# S100_Memory_Dumper.net
KiCad netlist of a schematic drawn in Altium Designer
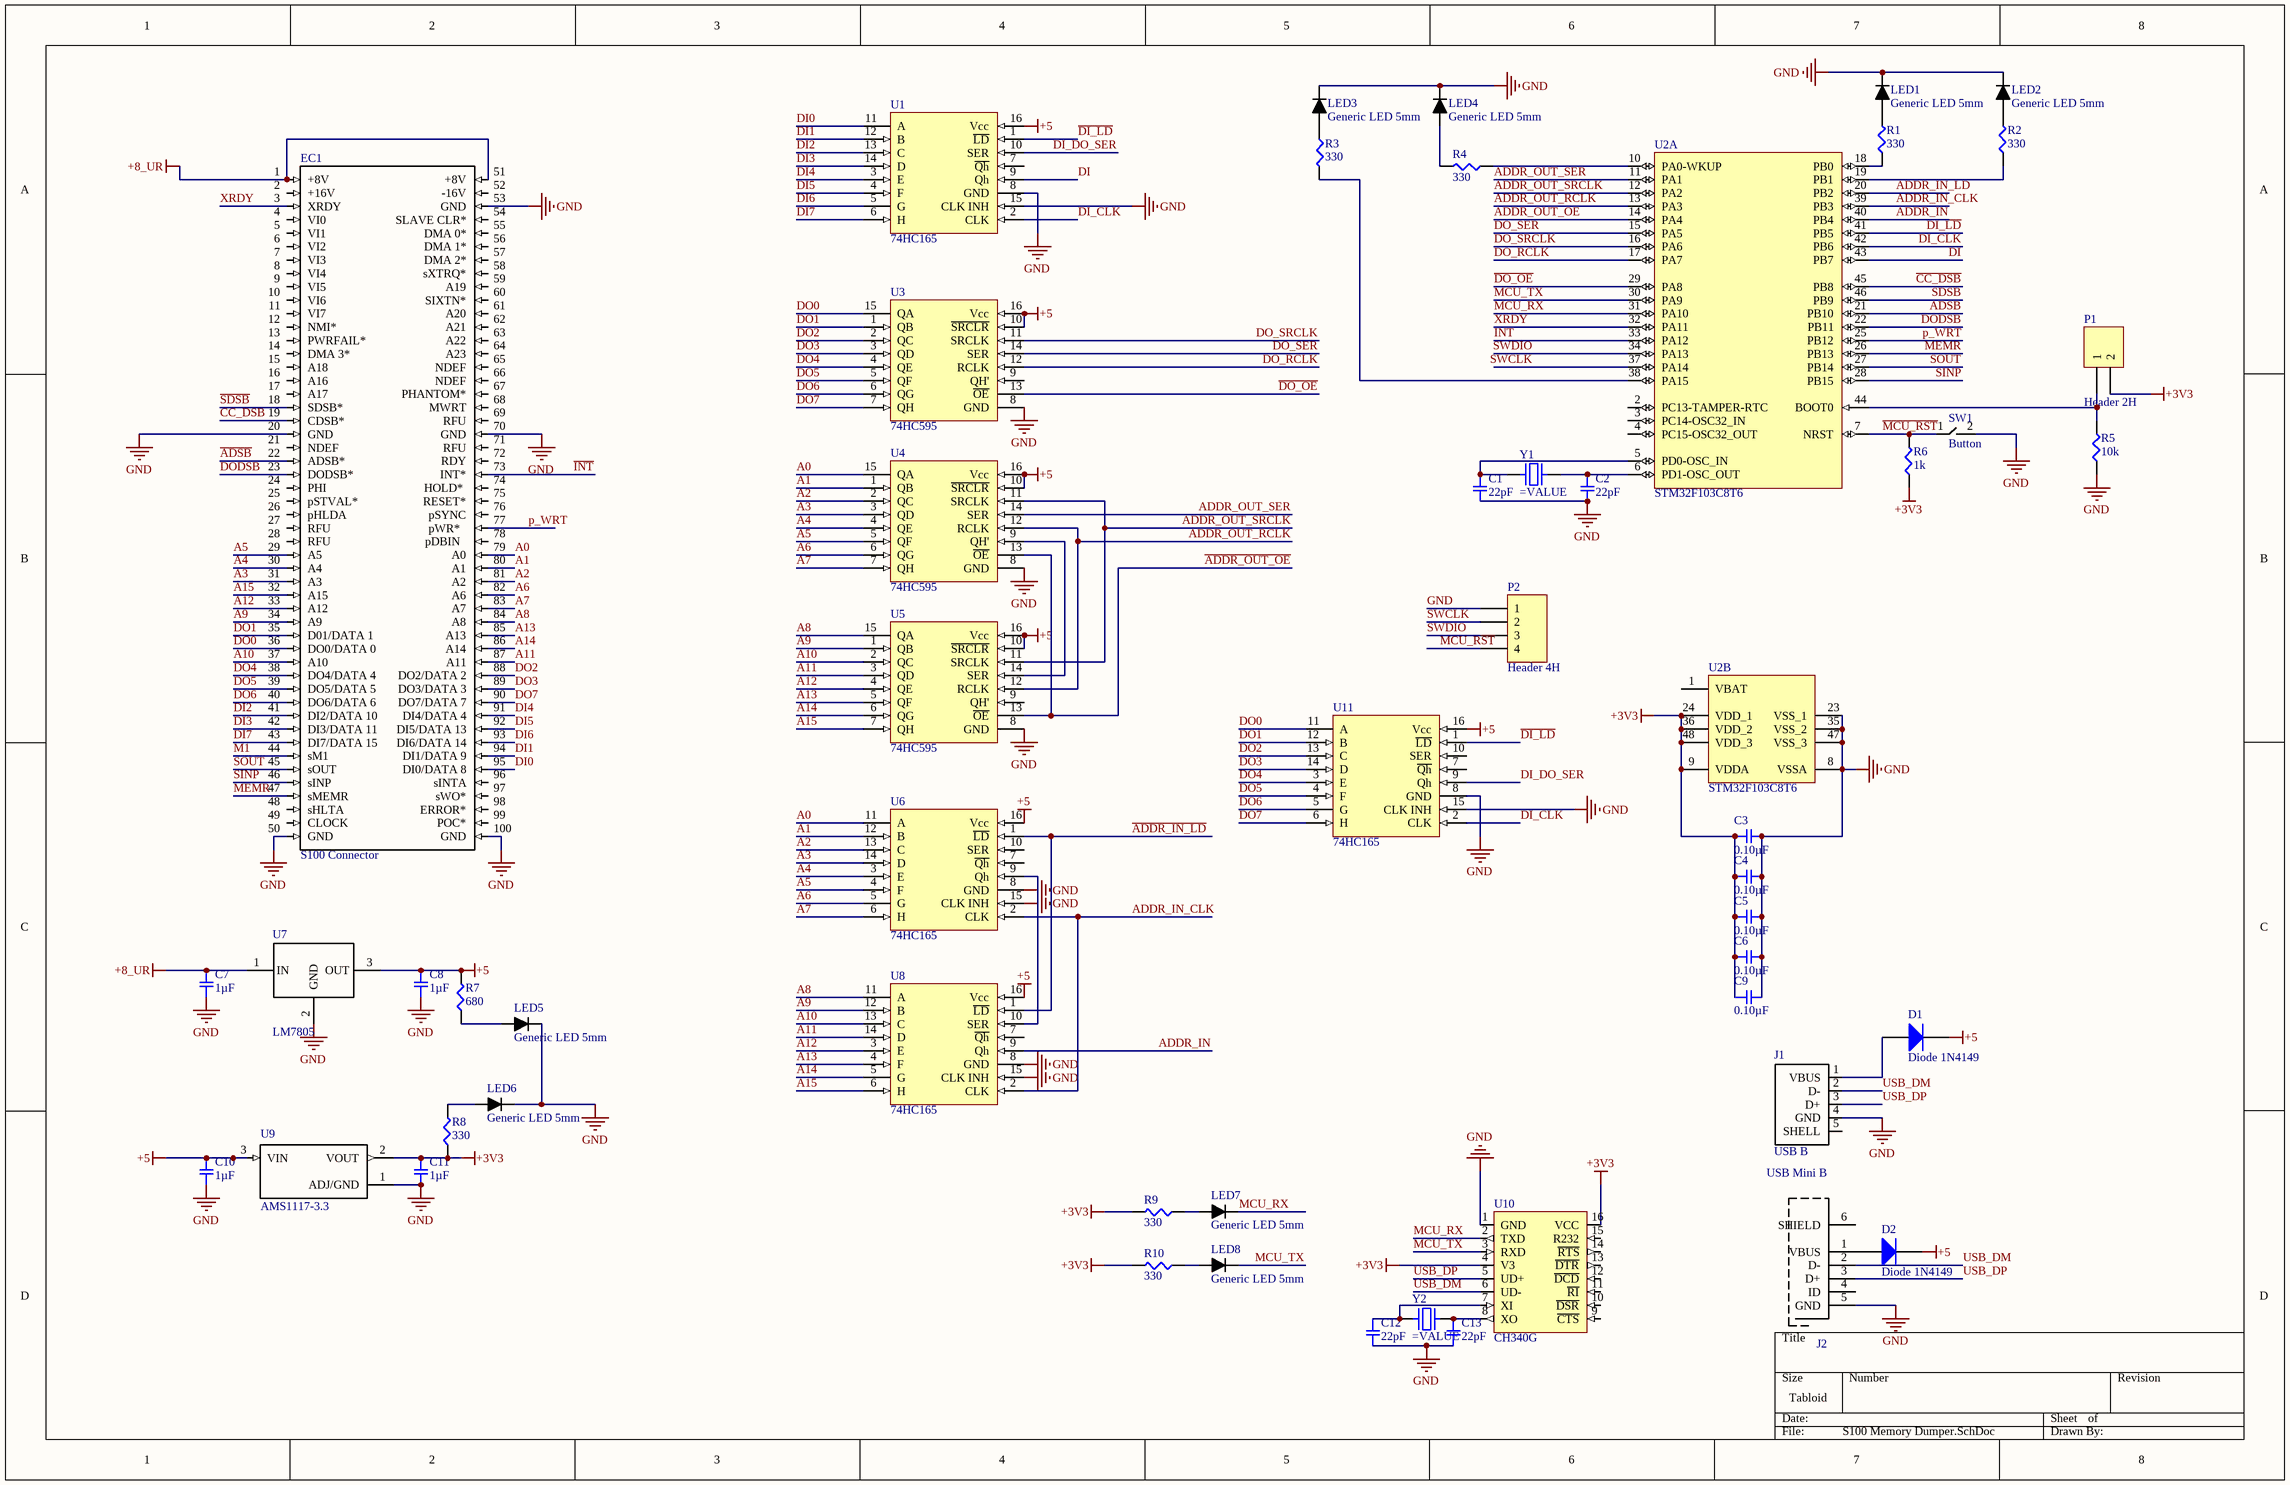
[diagram p0: S100 Memory Dumper.SchDoc]

(export (version "E")
  (design (tool "Eeschema 10.0.6"))
  (components
    (comp (ref "C1")
      (value "22pF")
      (footprint "SMD-0805C")
      (description "CAP CER 22PF 50V NP0 0805")
      (fields
        (field (name "DIGI-KEY PART NUMBER") "490-6097-1-ND")
        (field (name "PART NUMBER") "GQM2195C1H220GB01D")
      )
      (libsource (lib "capacitor_murata_0805") (part "GQM2195C1H220GB01D"))
    )
    (comp (ref "C2")
      (value "22pF")
      (footprint "SMD-0805C")
      (description "CAP CER 22PF 50V NP0 0805")
      (fields
        (field (name "DIGI-KEY PART NUMBER") "490-6097-1-ND")
        (field (name "PART NUMBER") "GQM2195C1H220GB01D")
      )
      (libsource (lib "capacitor_murata_0805") (part "GQM2195C1H220GB01D"))
    )
    (comp (ref "C3")
      (value "0.10µF")
      (footprint "SMD-0805C")
      (description "CAP CER 0.1UF 50V X7R 0805")
      (fields
        (field (name "DIGI-KEY PART NUMBER") "490-11955-1-ND")
        (field (name "PART NUMBER") "GCD21BR71H104KA01L")
      )
      (libsource (lib "capacitor_murata_0805") (part "GCD21BR71H104KA01L"))
    )
    (comp (ref "C4")
      (value "0.10µF")
      (footprint "SMD-0805C")
      (description "CAP CER 0.1UF 50V X7R 0805")
      (fields
        (field (name "DIGI-KEY PART NUMBER") "490-11955-1-ND")
        (field (name "PART NUMBER") "GCD21BR71H104KA01L")
      )
      (libsource (lib "capacitor_murata_0805") (part "GCD21BR71H104KA01L"))
    )
    (comp (ref "C5")
      (value "0.10µF")
      (footprint "SMD-0805C")
      (description "CAP CER 0.1UF 50V X7R 0805")
      (fields
        (field (name "DIGI-KEY PART NUMBER") "490-11955-1-ND")
        (field (name "PART NUMBER") "GCD21BR71H104KA01L")
      )
      (libsource (lib "capacitor_murata_0805") (part "GCD21BR71H104KA01L"))
    )
    (comp (ref "C6")
      (value "0.10µF")
      (footprint "SMD-0805C")
      (description "CAP CER 0.1UF 50V X7R 0805")
      (fields
        (field (name "DIGI-KEY PART NUMBER") "490-11955-1-ND")
        (field (name "PART NUMBER") "GCD21BR71H104KA01L")
      )
      (libsource (lib "capacitor_murata_0805") (part "GCD21BR71H104KA01L"))
    )
    (comp (ref "C7")
      (value "1µF")
      (footprint "SMD-0805C")
      (description "CAP CER 1UF 16V X7R 0805")
      (fields
        (field (name "DIGI-KEY PART NUMBER") "490-5800-1-ND")
        (field (name "PART NUMBER") "GCJ219R71C105KA01D")
      )
      (libsource (lib "capacitor_murata_0805") (part "GCJ219R71C105KA01D"))
    )
    (comp (ref "C8")
      (value "1µF")
      (footprint "SMD-0805C")
      (description "CAP CER 1UF 16V X7R 0805")
      (fields
        (field (name "DIGI-KEY PART NUMBER") "490-5800-1-ND")
        (field (name "PART NUMBER") "GCJ219R71C105KA01D")
      )
      (libsource (lib "capacitor_murata_0805") (part "GCJ219R71C105KA01D"))
    )
    (comp (ref "C9")
      (value "0.10µF")
      (footprint "SMD-0805C")
      (description "CAP CER 0.1UF 50V X7R 0805")
      (fields
        (field (name "DIGI-KEY PART NUMBER") "490-11955-1-ND")
        (field (name "PART NUMBER") "GCD21BR71H104KA01L")
      )
      (libsource (lib "capacitor_murata_0805") (part "GCD21BR71H104KA01L"))
    )
    (comp (ref "C10")
      (value "1µF")
      (footprint "SMD-0805C")
      (description "CAP CER 1UF 16V X7R 0805")
      (fields
        (field (name "DIGI-KEY PART NUMBER") "490-5800-1-ND")
        (field (name "PART NUMBER") "GCJ219R71C105KA01D")
      )
      (libsource (lib "capacitor_murata_0805") (part "GCJ219R71C105KA01D"))
    )
    (comp (ref "C11")
      (value "1µF")
      (footprint "SMD-0805C")
      (description "CAP CER 1UF 16V X7R 0805")
      (fields
        (field (name "DIGI-KEY PART NUMBER") "490-5800-1-ND")
        (field (name "PART NUMBER") "GCJ219R71C105KA01D")
      )
      (libsource (lib "capacitor_murata_0805") (part "GCJ219R71C105KA01D"))
    )
    (comp (ref "C12")
      (value "22pF")
      (footprint "SMD-0805C")
      (description "CAP CER 22PF 50V NP0 0805")
      (fields
        (field (name "DIGI-KEY PART NUMBER") "490-6097-1-ND")
        (field (name "PART NUMBER") "GQM2195C1H220GB01D")
      )
      (libsource (lib "capacitor_murata_0805") (part "GQM2195C1H220GB01D"))
    )
    (comp (ref "C13")
      (value "22pF")
      (footprint "SMD-0805C")
      (description "CAP CER 22PF 50V NP0 0805")
      (fields
        (field (name "DIGI-KEY PART NUMBER") "490-6097-1-ND")
        (field (name "PART NUMBER") "GQM2195C1H220GB01D")
      )
      (libsource (lib "capacitor_murata_0805") (part "GQM2195C1H220GB01D"))
    )
    (comp (ref "D1")
      (value "Diode 1N4149")
      (footprint "DO-35A")
      (description "Computer Diode")
      (fields (field (name "PUBLISHER") "Altium Limited"))
      (libsource (lib "Miscellaneous Devices") (part "Diode 1N4149"))
    )
    (comp (ref "D2")
      (value "Diode 1N4149")
      (footprint "DO-35A")
      (description "Computer Diode")
      (fields (field (name "PUBLISHER") "Altium Limited"))
      (libsource (lib "Miscellaneous Devices") (part "Diode 1N4149"))
    )
    (comp (ref "EC1")
      (value "S100 Connector")
      (footprint "S100")
      (libsource (lib "S100 Breakout SCHLIB") (part "S100 Connector"))
    )
    (comp (ref "J1")
      (value "USB B")
      (footprint "USB B V")
      (libsource (lib "S100 Memory Dumper SCHLIB") (part "USB B"))
    )
    (comp (ref "J2")
      (value "USB Mini B")
      (footprint "USB Mini B")
      (description "MINI USB A - 5POS Horizontal through hole")
      (fields (field (name "MF") "Wurth Electronics") (field (name "MP") "651005136521"))
      (libsource (lib "S100 Memory Dumper SCHLIB") (part "USB Mini B"))
    )
    (comp (ref "LED1")
      (value "Generic LED 5mm")
      (footprint "LED 5mm THT")
      (libsource (lib "Linear Regulators") (part "Generic LED 5mm"))
    )
    (comp (ref "LED2")
      (value "Generic LED 5mm")
      (footprint "LED 5mm THT")
      (libsource (lib "Linear Regulators") (part "Generic LED 5mm"))
    )
    (comp (ref "LED3")
      (value "Generic LED 5mm")
      (footprint "LED 5mm THT")
      (libsource (lib "Linear Regulators") (part "Generic LED 5mm"))
    )
    (comp (ref "LED4")
      (value "Generic LED 5mm")
      (footprint "LED 5mm THT")
      (libsource (lib "Linear Regulators") (part "Generic LED 5mm"))
    )
    (comp (ref "LED5")
      (value "Generic LED 5mm")
      (footprint "LED 5mm THT")
      (libsource (lib "Linear Regulators") (part "Generic LED 5mm"))
    )
    (comp (ref "LED6")
      (value "Generic LED 5mm")
      (footprint "LED 5mm THT")
      (libsource (lib "Linear Regulators") (part "Generic LED 5mm"))
    )
    (comp (ref "LED7")
      (value "Generic LED 5mm")
      (footprint "LED 5mm THT")
      (libsource (lib "Linear Regulators") (part "Generic LED 5mm"))
    )
    (comp (ref "LED8")
      (value "Generic LED 5mm")
      (footprint "LED 5mm THT")
      (libsource (lib "Linear Regulators") (part "Generic LED 5mm"))
    )
    (comp (ref "P1")
      (value "Header 2H")
      (footprint "HDR1X2H")
      (description "Header, 2-Pin, Right Angle")
      (fields (field (name "PUBLISHER") "Altium Limited"))
      (libsource (lib "Miscellaneous Connectors") (part "Header 2H"))
    )
    (comp (ref "P2")
      (value "Header 4H")
      (footprint "HDR1X4H")
      (description "Header, 4-Pin, Right Angle")
      (fields (field (name "PUBLISHER") "Altium Limited"))
      (libsource (lib "Miscellaneous Connectors") (part "Header 4H"))
    )
    (comp (ref "R1")
      (value "330")
      (footprint "SMD-0805-RES")
      (description "RES SMD 330 OHM 1% 1/8W 0805")
      (fields (field (name "PART NUMBER") "ERJ-6ENF3300V") (field (name "DIGI-KEY PART NUMBER") "P330CCT-ND"))
      (libsource (lib "Panasonic_ERJ_0805") (part "ERJ-6ENF3300V"))
    )
    (comp (ref "R2")
      (value "330")
      (footprint "SMD-0805-RES")
      (description "RES SMD 330 OHM 1% 1/8W 0805")
      (fields (field (name "PART NUMBER") "ERJ-6ENF3300V") (field (name "DIGI-KEY PART NUMBER") "P330CCT-ND"))
      (libsource (lib "Panasonic_ERJ_0805") (part "ERJ-6ENF3300V"))
    )
    (comp (ref "R3")
      (value "330")
      (footprint "SMD-0805-RES")
      (description "RES SMD 330 OHM 1% 1/8W 0805")
      (fields (field (name "PART NUMBER") "ERJ-6ENF3300V") (field (name "DIGI-KEY PART NUMBER") "P330CCT-ND"))
      (libsource (lib "Panasonic_ERJ_0805") (part "ERJ-6ENF3300V"))
    )
    (comp (ref "R4")
      (value "330")
      (footprint "SMD-0805-RES")
      (description "RES SMD 330 OHM 1% 1/8W 0805")
      (fields (field (name "PART NUMBER") "ERJ-6ENF3300V") (field (name "DIGI-KEY PART NUMBER") "P330CCT-ND"))
      (libsource (lib "Panasonic_ERJ_0805") (part "ERJ-6ENF3300V"))
    )
    (comp (ref "R5")
      (value "10k")
      (footprint "SMD-0805-RES")
      (description "RES SMD 10K OHM 1% 1/2W 0805")
      (fields
        (field (name "PART NUMBER") "ERJ-P06F1002V")
        (field (name "DIGI-KEY PART NUMBER") "P16059CT-ND")
      )
      (libsource (lib "Panasonic_ERJ_0805") (part "ERJ-P06F1002V"))
    )
    (comp (ref "R6")
      (value "1k")
      (footprint "SMD-0805-RES")
      (description "RES SMD 1K OHM 1% 1/2W 0805")
      (fields
        (field (name "PART NUMBER") "ERJ-P06F1001V")
        (field (name "DIGI-KEY PART NUMBER") "P16058CT-ND")
      )
      (libsource (lib "Panasonic_ERJ_0805") (part "ERJ-P06F1001V"))
    )
    (comp (ref "R7")
      (value "680")
      (footprint "SMD-0805-RES")
      (description "RES SMD 680 OHM 1% 1/8W 0805")
      (fields (field (name "PART NUMBER") "ERJ-6ENF6800V") (field (name "DIGI-KEY PART NUMBER") "P680CCT-ND"))
      (libsource (lib "Panasonic_ERJ_0805") (part "ERJ-6ENF6800V"))
    )
    (comp (ref "R8")
      (value "330")
      (footprint "SMD-0805-RES")
      (description "RES SMD 330 OHM 1% 1/8W 0805")
      (fields (field (name "PART NUMBER") "ERJ-6ENF3300V") (field (name "DIGI-KEY PART NUMBER") "P330CCT-ND"))
      (libsource (lib "Panasonic_ERJ_0805") (part "ERJ-6ENF3300V"))
    )
    (comp (ref "R9")
      (value "330")
      (footprint "SMD-0805-RES")
      (description "RES SMD 330 OHM 1% 1/8W 0805")
      (fields (field (name "PART NUMBER") "ERJ-6ENF3300V") (field (name "DIGI-KEY PART NUMBER") "P330CCT-ND"))
      (libsource (lib "Panasonic_ERJ_0805") (part "ERJ-6ENF3300V"))
    )
    (comp (ref "R10")
      (value "330")
      (footprint "SMD-0805-RES")
      (description "RES SMD 330 OHM 1% 1/8W 0805")
      (fields (field (name "PART NUMBER") "ERJ-6ENF3300V") (field (name "DIGI-KEY PART NUMBER") "P330CCT-ND"))
      (libsource (lib "Panasonic_ERJ_0805") (part "ERJ-6ENF3300V"))
    )
    (comp (ref "SW1")
      (value "Button")
      (footprint "SMD_PUSHBUTTON_LCSC")
      (description "LCSC Push button SMD")
      (libsource (lib "Linear Regulators") (part "Button"))
    )
    (comp (ref "U1")
      (value "74HC165")
      (footprint "S100 Memory Dumper:SOIC-175-16")
      (libsource (lib "S100 Memory Dumper SCHLIB") (part "74HC165"))
    )
    (comp (ref "U2")
      (value "STM32F103C8T6")
      (footprint "STM-LQFP48_N")
      (libsource (lib "STMicroelectronics STM32 F1") (part "STM32F103C8T6"))
    )
    (comp (ref "U3")
      (value "74HC595")
      (footprint "S100 Memory Dumper:SOIC-175-16")
      (libsource (lib "S100 Memory Dumper SCHLIB") (part "74HC595"))
    )
    (comp (ref "U4")
      (value "74HC595")
      (footprint "S100 Memory Dumper:SOIC-175-16")
      (libsource (lib "S100 Memory Dumper SCHLIB") (part "74HC595"))
    )
    (comp (ref "U5")
      (value "74HC595")
      (footprint "S100 Memory Dumper:SOIC-175-16")
      (libsource (lib "S100 Memory Dumper SCHLIB") (part "74HC595"))
    )
    (comp (ref "U6")
      (value "74HC165")
      (footprint "S100 Memory Dumper:SOIC-175-16")
      (libsource (lib "S100 Memory Dumper SCHLIB") (part "74HC165"))
    )
    (comp (ref "U7")
      (value "LM7805")
      (footprint "LM7805-TO220")
      (description "LM7805 Linear Voltage Regulator")
      (libsource (lib "Linear Regulators") (part "LM7805"))
    )
    (comp (ref "U8")
      (value "74HC165")
      (footprint "S100 Memory Dumper:SOIC-175-16")
      (libsource (lib "S100 Memory Dumper SCHLIB") (part "74HC165"))
    )
    (comp (ref "U9")
      (value "AMS1117-3.3")
      (footprint "AMS1117-3.3-SOT23")
      (description "Sot223/Pkg 1-Amp 3.3-Volt Low Drop Out Voltage Regulatator")
      (fields (field (name "MF") "Advanced Monolithic Systems"))
      (libsource (lib "Linear Regulators") (part "AMS1117-3.3"))
    )
    (comp (ref "U10")
      (value "CH340G")
      (footprint "SOIC-175-16")
      (libsource (lib "S100 Memory Dumper SCHLIB") (part "CH340G"))
    )
    (comp (ref "U11")
      (value "74HC165")
      (footprint "S100 Memory Dumper:SOIC-175-16")
      (libsource (lib "S100 Memory Dumper SCHLIB") (part "74HC165"))
    )
    (comp (ref "Y1")
      (value "~")
      (footprint "ABRACON ABLS")
      (description "SMT Crystal")
      (libsource (lib "Linear Regulators") (part "Abracon Crystal ABLS"))
    )
    (comp (ref "Y2")
      (value "~")
      (footprint "THT_Crystal")
      (description "SMT Crystal")
      (libsource (lib "Linear Regulators") (part "THT Crystal"))
    )
  )
  (nets
    (net (code "1") (name "+3V3") (class "Default")
      (node (ref "C11") (pin "1") (pinfunction "1_1") (pintype "passive"))
      (node (ref "C3") (pin "1") (pinfunction "1_1") (pintype "passive"))
      (node (ref "C4") (pin "1") (pinfunction "1_1") (pintype "passive"))
      (node (ref "C5") (pin "1") (pinfunction "1_1") (pintype "passive"))
      (node (ref "C6") (pin "1") (pinfunction "1_1") (pintype "passive"))
      (node (ref "C9") (pin "1") (pinfunction "1_1") (pintype "passive"))
      (node (ref "P1") (pin "2") (pinfunction "2_2") (pintype "passive"))
      (node (ref "R10") (pin "2") (pinfunction "2_2") (pintype "passive"))
      (node (ref "R6") (pin "1") (pinfunction "1_1") (pintype "passive"))
      (node (ref "R8") (pin "1") (pinfunction "1_1") (pintype "passive"))
      (node (ref "R9") (pin "2") (pinfunction "2_2") (pintype "passive"))
      (node (ref "U10") (pin "16") (pinfunction "VCC_16") (pintype "power_in"))
      (node (ref "U10") (pin "4") (pinfunction "V3_4") (pintype "power_in"))
      (node (ref "U2") (pin "24") (pinfunction "VDD_1_24") (pintype "power_in"))
      (node (ref "U2") (pin "36") (pinfunction "VDD_2_36") (pintype "power_in"))
      (node (ref "U2") (pin "48") (pinfunction "VDD_3_48") (pintype "power_in"))
      (node (ref "U2") (pin "9") (pinfunction "VDDA_9") (pintype "power_in"))
      (node (ref "U9") (pin "2") (pinfunction "VOUT_2") (pintype "output"))
    )
    (net (code "2") (name "+5") (class "Default")
      (node (ref "C10") (pin "1") (pinfunction "1_1") (pintype "passive"))
      (node (ref "C8") (pin "1") (pinfunction "1_1") (pintype "passive"))
      (node (ref "D1") (pin "2") (pinfunction "K_2") (pintype "passive"))
      (node (ref "D2") (pin "2") (pinfunction "K_2") (pintype "passive"))
      (node (ref "R7") (pin "2") (pinfunction "2_2") (pintype "passive"))
      (node (ref "U1") (pin "16") (pinfunction "Vcc_16") (pintype "input"))
      (node (ref "U11") (pin "16") (pinfunction "Vcc_16") (pintype "input"))
      (node (ref "U3") (pin "10") (pinfunction "SRCLR_10") (pintype "input"))
      (node (ref "U3") (pin "16") (pinfunction "Vcc_16") (pintype "input"))
      (node (ref "U4") (pin "10") (pinfunction "SRCLR_10") (pintype "input"))
      (node (ref "U4") (pin "16") (pinfunction "Vcc_16") (pintype "input"))
      (node (ref "U5") (pin "10") (pinfunction "SRCLR_10") (pintype "input"))
      (node (ref "U5") (pin "16") (pinfunction "Vcc_16") (pintype "input"))
      (node (ref "U6") (pin "16") (pinfunction "Vcc_16") (pintype "input"))
      (node (ref "U7") (pin "3") (pinfunction "OUT_3") (pintype "passive"))
      (node (ref "U8") (pin "16") (pinfunction "Vcc_16") (pintype "input"))
      (node (ref "U9") (pin "3") (pinfunction "VIN_3") (pintype "input"))
    )
    (net (code "3") (name "+8_UR") (class "Default")
      (node (ref "C7") (pin "1") (pinfunction "1_1") (pintype "passive"))
      (node (ref "EC1") (pin "1") (pinfunction "+8V_1") (pintype "input"))
      (node (ref "EC1") (pin "51") (pinfunction "+8V_51") (pintype "input"))
      (node (ref "U7") (pin "1") (pinfunction "IN_1") (pintype "passive"))
    )
    (net (code "4") (name "/A0") (class "Default")
      (node (ref "EC1") (pin "79") (pinfunction "A0_79") (pintype "input"))
      (node (ref "U4") (pin "15") (pinfunction "QA_15") (pintype "passive"))
      (node (ref "U6") (pin "11") (pinfunction "A_11") (pintype "passive"))
    )
    (net (code "5") (name "/A1") (class "Default")
      (node (ref "EC1") (pin "80") (pinfunction "A1_80") (pintype "input"))
      (node (ref "U4") (pin "1") (pinfunction "QB_1") (pintype "input"))
      (node (ref "U6") (pin "12") (pinfunction "B_12") (pintype "input"))
    )
    (net (code "6") (name "/A2") (class "Default")
      (node (ref "EC1") (pin "81") (pinfunction "A2_81") (pintype "input"))
      (node (ref "U4") (pin "2") (pinfunction "QC_2") (pintype "input"))
      (node (ref "U6") (pin "13") (pinfunction "C_13") (pintype "input"))
    )
    (net (code "7") (name "/A3") (class "Default")
      (node (ref "EC1") (pin "31") (pinfunction "A3_31") (pintype "input"))
      (node (ref "U4") (pin "3") (pinfunction "QD_3") (pintype "input"))
      (node (ref "U6") (pin "14") (pinfunction "D_14") (pintype "input"))
    )
    (net (code "8") (name "/A4") (class "Default")
      (node (ref "EC1") (pin "30") (pinfunction "A4_30") (pintype "input"))
      (node (ref "U4") (pin "4") (pinfunction "QE_4") (pintype "input"))
      (node (ref "U6") (pin "3") (pinfunction "E_3") (pintype "input"))
    )
    (net (code "9") (name "/A5") (class "Default")
      (node (ref "EC1") (pin "29") (pinfunction "A5_29") (pintype "input"))
      (node (ref "U4") (pin "5") (pinfunction "QF_5") (pintype "input"))
      (node (ref "U6") (pin "4") (pinfunction "F_4") (pintype "input"))
    )
    (net (code "10") (name "/A6") (class "Default")
      (node (ref "EC1") (pin "82") (pinfunction "A6_82") (pintype "input"))
      (node (ref "U4") (pin "6") (pinfunction "QG_6") (pintype "input"))
      (node (ref "U6") (pin "5") (pinfunction "G_5") (pintype "passive"))
    )
    (net (code "11") (name "/A7") (class "Default")
      (node (ref "EC1") (pin "83") (pinfunction "A7_83") (pintype "input"))
      (node (ref "U4") (pin "7") (pinfunction "QH_7") (pintype "input"))
      (node (ref "U6") (pin "6") (pinfunction "H_6") (pintype "input"))
    )
    (net (code "12") (name "/A8") (class "Default")
      (node (ref "EC1") (pin "84") (pinfunction "A8_84") (pintype "input"))
      (node (ref "U5") (pin "15") (pinfunction "QA_15") (pintype "passive"))
      (node (ref "U8") (pin "11") (pinfunction "A_11") (pintype "passive"))
    )
    (net (code "13") (name "/A9") (class "Default")
      (node (ref "EC1") (pin "34") (pinfunction "A9_34") (pintype "input"))
      (node (ref "U5") (pin "1") (pinfunction "QB_1") (pintype "input"))
      (node (ref "U8") (pin "12") (pinfunction "B_12") (pintype "input"))
    )
    (net (code "14") (name "/A10") (class "Default")
      (node (ref "EC1") (pin "37") (pinfunction "A10_37") (pintype "input"))
      (node (ref "U5") (pin "2") (pinfunction "QC_2") (pintype "input"))
      (node (ref "U8") (pin "13") (pinfunction "C_13") (pintype "input"))
    )
    (net (code "15") (name "/A11") (class "Default")
      (node (ref "EC1") (pin "87") (pinfunction "A11_87") (pintype "input"))
      (node (ref "U5") (pin "3") (pinfunction "QD_3") (pintype "input"))
      (node (ref "U8") (pin "14") (pinfunction "D_14") (pintype "input"))
    )
    (net (code "16") (name "/A12") (class "Default")
      (node (ref "EC1") (pin "33") (pinfunction "A12_33") (pintype "input"))
      (node (ref "U5") (pin "4") (pinfunction "QE_4") (pintype "input"))
      (node (ref "U8") (pin "3") (pinfunction "E_3") (pintype "input"))
    )
    (net (code "17") (name "/A13") (class "Default")
      (node (ref "EC1") (pin "85") (pinfunction "A13_85") (pintype "input"))
      (node (ref "U5") (pin "5") (pinfunction "QF_5") (pintype "input"))
      (node (ref "U8") (pin "4") (pinfunction "F_4") (pintype "input"))
    )
    (net (code "18") (name "/A14") (class "Default")
      (node (ref "EC1") (pin "86") (pinfunction "A14_86") (pintype "input"))
      (node (ref "U5") (pin "6") (pinfunction "QG_6") (pintype "input"))
      (node (ref "U8") (pin "5") (pinfunction "G_5") (pintype "passive"))
    )
    (net (code "19") (name "/A15") (class "Default")
      (node (ref "EC1") (pin "32") (pinfunction "A15_32") (pintype "input"))
      (node (ref "U5") (pin "7") (pinfunction "QH_7") (pintype "input"))
      (node (ref "U8") (pin "6") (pinfunction "H_6") (pintype "input"))
    )
    (net (code "20") (name "/ADDR_IN") (class "Default")
      (node (ref "U2") (pin "40") (pinfunction "PB4_40") (pintype "bidirectional"))
      (node (ref "U8") (pin "9") (pinfunction "Qh_9") (pintype "input"))
    )
    (net (code "21") (name "/ADDR_IN_CLK") (class "Default")
      (node (ref "U2") (pin "39") (pinfunction "PB3_39") (pintype "bidirectional"))
      (node (ref "U6") (pin "2") (pinfunction "CLK_2") (pintype "input"))
      (node (ref "U8") (pin "2") (pinfunction "CLK_2") (pintype "input"))
    )
    (net (code "22") (name "/ADDR_IN_LD") (class "Default")
      (node (ref "U2") (pin "20") (pinfunction "PB2_20") (pintype "bidirectional"))
      (node (ref "U6") (pin "1") (pinfunction "LD_1") (pintype "input"))
      (node (ref "U8") (pin "1") (pinfunction "LD_1") (pintype "input"))
    )
    (net (code "23") (name "/ADDR_OUT_OE") (class "Default")
      (node (ref "U2") (pin "14") (pinfunction "PA4_14") (pintype "bidirectional"))
      (node (ref "U4") (pin "13") (pinfunction "OE_13") (pintype "passive"))
      (node (ref "U5") (pin "13") (pinfunction "OE_13") (pintype "passive"))
    )
    (net (code "24") (name "/ADDR_OUT_RCLK") (class "Default")
      (node (ref "U2") (pin "13") (pinfunction "PA3_13") (pintype "bidirectional"))
      (node (ref "U4") (pin "12") (pinfunction "RCLK_12") (pintype "input"))
      (node (ref "U5") (pin "12") (pinfunction "RCLK_12") (pintype "input"))
    )
    (net (code "25") (name "/ADDR_OUT_SER") (class "Default")
      (node (ref "U2") (pin "11") (pinfunction "PA1_11") (pintype "bidirectional"))
      (node (ref "U4") (pin "14") (pinfunction "SER_14") (pintype "input"))
    )
    (net (code "26") (name "/ADDR_OUT_SRCLK") (class "Default")
      (node (ref "U2") (pin "12") (pinfunction "PA2_12") (pintype "bidirectional"))
      (node (ref "U4") (pin "11") (pinfunction "SRCLK_11") (pintype "input"))
      (node (ref "U5") (pin "11") (pinfunction "SRCLK_11") (pintype "input"))
    )
    (net (code "27") (name "/ADSB") (class "Default")
      (node (ref "EC1") (pin "22") (pinfunction "ADSB*_22") (pintype "input"))
      (node (ref "U2") (pin "21") (pinfunction "PB10_21") (pintype "bidirectional"))
    )
    (net (code "28") (name "/CC_DSB") (class "Default")
      (node (ref "EC1") (pin "19") (pinfunction "CDSB*_19") (pintype "input"))
      (node (ref "U2") (pin "45") (pinfunction "PB8_45") (pintype "bidirectional"))
    )
    (net (code "29") (name "/DI") (class "Default")
      (node (ref "U1") (pin "9") (pinfunction "Qh_9") (pintype "input"))
      (node (ref "U2") (pin "43") (pinfunction "PB7_43") (pintype "bidirectional"))
    )
    (net (code "30") (name "/DI0") (class "Default")
      (node (ref "EC1") (pin "95") (pinfunction "DI0/DATA_8_95") (pintype "input"))
      (node (ref "U1") (pin "11") (pinfunction "A_11") (pintype "passive"))
    )
    (net (code "31") (name "/DI1") (class "Default")
      (node (ref "EC1") (pin "94") (pinfunction "DI1/DATA_9_94") (pintype "input"))
      (node (ref "U1") (pin "12") (pinfunction "B_12") (pintype "input"))
    )
    (net (code "32") (name "/DI2") (class "Default")
      (node (ref "EC1") (pin "41") (pinfunction "DI2/DATA_10_41") (pintype "input"))
      (node (ref "U1") (pin "13") (pinfunction "C_13") (pintype "input"))
    )
    (net (code "33") (name "/DI3") (class "Default")
      (node (ref "EC1") (pin "42") (pinfunction "DI3/DATA_11_42") (pintype "input"))
      (node (ref "U1") (pin "14") (pinfunction "D_14") (pintype "input"))
    )
    (net (code "34") (name "/DI4") (class "Default")
      (node (ref "EC1") (pin "91") (pinfunction "DI4/DATA_4_91") (pintype "input"))
      (node (ref "U1") (pin "3") (pinfunction "E_3") (pintype "input"))
    )
    (net (code "35") (name "/DI5") (class "Default")
      (node (ref "EC1") (pin "92") (pinfunction "DI5/DATA_13_92") (pintype "input"))
      (node (ref "U1") (pin "4") (pinfunction "F_4") (pintype "input"))
    )
    (net (code "36") (name "/DI6") (class "Default")
      (node (ref "EC1") (pin "93") (pinfunction "DI6/DATA_14_93") (pintype "input"))
      (node (ref "U1") (pin "5") (pinfunction "G_5") (pintype "passive"))
    )
    (net (code "37") (name "/DI7") (class "Default")
      (node (ref "EC1") (pin "43") (pinfunction "DI7/DATA_15_43") (pintype "input"))
      (node (ref "U1") (pin "6") (pinfunction "H_6") (pintype "input"))
    )
    (net (code "38") (name "/DI_CLK") (class "Default")
      (node (ref "U1") (pin "2") (pinfunction "CLK_2") (pintype "input"))
      (node (ref "U11") (pin "2") (pinfunction "CLK_2") (pintype "input"))
      (node (ref "U2") (pin "42") (pinfunction "PB6_42") (pintype "bidirectional"))
    )
    (net (code "39") (name "/DI_DO_SER") (class "Default")
      (node (ref "U1") (pin "10") (pinfunction "SER_10") (pintype "input"))
      (node (ref "U11") (pin "9") (pinfunction "Qh_9") (pintype "input"))
    )
    (net (code "40") (name "/DI_LD") (class "Default")
      (node (ref "U1") (pin "1") (pinfunction "LD_1") (pintype "input"))
      (node (ref "U11") (pin "1") (pinfunction "LD_1") (pintype "input"))
      (node (ref "U2") (pin "41") (pinfunction "PB5_41") (pintype "bidirectional"))
    )
    (net (code "41") (name "/DO0") (class "Default")
      (node (ref "EC1") (pin "36") (pinfunction "DO0/DATA_0_36") (pintype "input"))
      (node (ref "U11") (pin "11") (pinfunction "A_11") (pintype "passive"))
      (node (ref "U3") (pin "15") (pinfunction "QA_15") (pintype "passive"))
    )
    (net (code "42") (name "/DO1") (class "Default")
      (node (ref "EC1") (pin "35") (pinfunction "D01/DATA_1_35") (pintype "input"))
      (node (ref "U11") (pin "12") (pinfunction "B_12") (pintype "input"))
      (node (ref "U3") (pin "1") (pinfunction "QB_1") (pintype "input"))
    )
    (net (code "43") (name "/DO2") (class "Default")
      (node (ref "EC1") (pin "88") (pinfunction "DO2/DATA_2_88") (pintype "input"))
      (node (ref "U11") (pin "13") (pinfunction "C_13") (pintype "input"))
      (node (ref "U3") (pin "2") (pinfunction "QC_2") (pintype "input"))
    )
    (net (code "44") (name "/DO3") (class "Default")
      (node (ref "EC1") (pin "89") (pinfunction "DO3/DATA_3_89") (pintype "input"))
      (node (ref "U11") (pin "14") (pinfunction "D_14") (pintype "input"))
      (node (ref "U3") (pin "3") (pinfunction "QD_3") (pintype "input"))
    )
    (net (code "45") (name "/DO4") (class "Default")
      (node (ref "EC1") (pin "38") (pinfunction "DO4/DATA_4_38") (pintype "input"))
      (node (ref "U11") (pin "3") (pinfunction "E_3") (pintype "input"))
      (node (ref "U3") (pin "4") (pinfunction "QE_4") (pintype "input"))
    )
    (net (code "46") (name "/DO5") (class "Default")
      (node (ref "EC1") (pin "39") (pinfunction "DO5/DATA_5_39") (pintype "input"))
      (node (ref "U11") (pin "4") (pinfunction "F_4") (pintype "input"))
      (node (ref "U3") (pin "5") (pinfunction "QF_5") (pintype "input"))
    )
    (net (code "47") (name "/DO6") (class "Default")
      (node (ref "EC1") (pin "40") (pinfunction "DO6/DATA_6_40") (pintype "input"))
      (node (ref "U11") (pin "5") (pinfunction "G_5") (pintype "passive"))
      (node (ref "U3") (pin "6") (pinfunction "QG_6") (pintype "input"))
    )
    (net (code "48") (name "/DO7") (class "Default")
      (node (ref "EC1") (pin "90") (pinfunction "DO7/DATA_7_90") (pintype "input"))
      (node (ref "U11") (pin "6") (pinfunction "H_6") (pintype "input"))
      (node (ref "U3") (pin "7") (pinfunction "QH_7") (pintype "input"))
    )
    (net (code "49") (name "/DODSB") (class "Default")
      (node (ref "EC1") (pin "23") (pinfunction "DODSB*_23") (pintype "input"))
      (node (ref "U2") (pin "22") (pinfunction "PB11_22") (pintype "bidirectional"))
    )
    (net (code "50") (name "/DO_OE") (class "Default")
      (node (ref "U2") (pin "29") (pinfunction "PA8_29") (pintype "bidirectional"))
      (node (ref "U3") (pin "13") (pinfunction "OE_13") (pintype "passive"))
    )
    (net (code "51") (name "/DO_RCLK") (class "Default")
      (node (ref "U2") (pin "17") (pinfunction "PA7_17") (pintype "bidirectional"))
      (node (ref "U3") (pin "12") (pinfunction "RCLK_12") (pintype "input"))
    )
    (net (code "52") (name "/DO_SER") (class "Default")
      (node (ref "U2") (pin "15") (pinfunction "PA5_15") (pintype "bidirectional"))
      (node (ref "U3") (pin "14") (pinfunction "SER_14") (pintype "input"))
    )
    (net (code "53") (name "/DO_SRCLK") (class "Default")
      (node (ref "U2") (pin "16") (pinfunction "PA6_16") (pintype "bidirectional"))
      (node (ref "U3") (pin "11") (pinfunction "SRCLK_11") (pintype "input"))
    )
    (net (code "54") (name "/INT") (class "Default")
      (node (ref "EC1") (pin "73") (pinfunction "INT*_73") (pintype "input"))
      (node (ref "U2") (pin "33") (pinfunction "PA12_33") (pintype "bidirectional"))
    )
    (net (code "55") (name "/M1") (class "Default")
      (node (ref "EC1") (pin "44") (pinfunction "sM1_44") (pintype "input"))
    )
    (net (code "56") (name "/MCU_RST") (class "Default")
      (node (ref "P2") (pin "4") (pinfunction "4_4") (pintype "passive"))
      (node (ref "R6") (pin "2") (pinfunction "2_2") (pintype "passive"))
      (node (ref "SW1") (pin "1") (pintype "passive"))
      (node (ref "U2") (pin "7") (pinfunction "NRST_7") (pintype "bidirectional"))
    )
    (net (code "57") (name "/MCU_RX") (class "Default")
      (node (ref "LED7") (pin "2") (pinfunction "K_2") (pintype "passive"))
      (node (ref "U10") (pin "2") (pinfunction "TXD_2") (pintype "output"))
      (node (ref "U2") (pin "31") (pinfunction "PA10_31") (pintype "bidirectional"))
    )
    (net (code "58") (name "/MCU_TX") (class "Default")
      (node (ref "LED8") (pin "2") (pinfunction "K_2") (pintype "passive"))
      (node (ref "U10") (pin "3") (pinfunction "RXD_3") (pintype "input"))
      (node (ref "U2") (pin "30") (pinfunction "PA9_30") (pintype "bidirectional"))
    )
    (net (code "59") (name "/MEMR") (class "Default")
      (node (ref "EC1") (pin "47") (pinfunction "sMEMR_47") (pintype "input"))
      (node (ref "U2") (pin "26") (pinfunction "PB13_26") (pintype "bidirectional"))
    )
    (net (code "60") (name "/SDSB") (class "Default")
      (node (ref "EC1") (pin "18") (pinfunction "SDSB*_18") (pintype "input"))
      (node (ref "U2") (pin "46") (pinfunction "PB9_46") (pintype "bidirectional"))
    )
    (net (code "61") (name "/SINP") (class "Default")
      (node (ref "EC1") (pin "46") (pinfunction "sINP_46") (pintype "input"))
      (node (ref "U2") (pin "28") (pinfunction "PB15_28") (pintype "bidirectional"))
    )
    (net (code "62") (name "/SOUT") (class "Default")
      (node (ref "EC1") (pin "45") (pinfunction "sOUT_45") (pintype "input"))
      (node (ref "U2") (pin "27") (pinfunction "PB14_27") (pintype "bidirectional"))
    )
    (net (code "63") (name "/SWCLK") (class "Default")
      (node (ref "P2") (pin "2") (pinfunction "2_2") (pintype "passive"))
      (node (ref "U2") (pin "37") (pinfunction "PA14_37") (pintype "bidirectional"))
    )
    (net (code "64") (name "/SWDIO") (class "Default")
      (node (ref "P2") (pin "3") (pinfunction "3_3") (pintype "passive"))
      (node (ref "U2") (pin "34") (pinfunction "PA13_34") (pintype "bidirectional"))
    )
    (net (code "65") (name "/USB_DM") (class "Default")
      (node (ref "J1") (pin "2") (pinfunction "D-_2") (pintype "passive"))
      (node (ref "J2") (pin "2") (pinfunction "D-_2") (pintype "passive"))
      (node (ref "U10") (pin "6") (pinfunction "UD-_6") (pintype "bidirectional"))
    )
    (net (code "66") (name "/USB_DP") (class "Default")
      (node (ref "J1") (pin "3") (pinfunction "D+_3") (pintype "passive"))
      (node (ref "J2") (pin "3") (pinfunction "D+_3") (pintype "passive"))
      (node (ref "U10") (pin "5") (pinfunction "UD+_5") (pintype "bidirectional"))
    )
    (net (code "67") (name "/XRDY") (class "Default")
      (node (ref "EC1") (pin "3") (pinfunction "XRDY_3") (pintype "input"))
      (node (ref "U2") (pin "32") (pinfunction "PA11_32") (pintype "bidirectional"))
    )
    (net (code "68") (name "/p_WRT") (class "Default")
      (node (ref "EC1") (pin "77") (pinfunction "pWR*  _77") (pintype "input"))
      (node (ref "U2") (pin "25") (pinfunction "PB12_25") (pintype "bidirectional"))
    )
    (net (code "69") (name "GND") (class "Default")
      (node (ref "C1") (pin "2") (pinfunction "2_2") (pintype "passive"))
      (node (ref "C10") (pin "2") (pinfunction "2_2") (pintype "passive"))
      (node (ref "C11") (pin "2") (pinfunction "2_2") (pintype "passive"))
      (node (ref "C12") (pin "2") (pinfunction "2_2") (pintype "passive"))
      (node (ref "C13") (pin "2") (pinfunction "2_2") (pintype "passive"))
      (node (ref "C2") (pin "2") (pinfunction "2_2") (pintype "passive"))
      (node (ref "C3") (pin "2") (pinfunction "2_2") (pintype "passive"))
      (node (ref "C4") (pin "2") (pinfunction "2_2") (pintype "passive"))
      (node (ref "C5") (pin "2") (pinfunction "2_2") (pintype "passive"))
      (node (ref "C6") (pin "2") (pinfunction "2_2") (pintype "passive"))
      (node (ref "C7") (pin "2") (pinfunction "2_2") (pintype "passive"))
      (node (ref "C8") (pin "2") (pinfunction "2_2") (pintype "passive"))
      (node (ref "C9") (pin "2") (pinfunction "2_2") (pintype "passive"))
      (node (ref "EC1") (pin "100") (pinfunction "GND_100") (pintype "input"))
      (node (ref "EC1") (pin "20") (pinfunction "GND_20") (pintype "input"))
      (node (ref "EC1") (pin "50") (pinfunction "GND_50") (pintype "input"))
      (node (ref "EC1") (pin "53") (pinfunction "GND_53") (pintype "input"))
      (node (ref "EC1") (pin "70") (pinfunction "GND_70") (pintype "input"))
      (node (ref "J1") (pin "4") (pinfunction "GND_4") (pintype "passive"))
      (node (ref "J2") (pin "5") (pinfunction "GND_5") (pintype "passive"))
      (node (ref "LED1") (pin "2") (pinfunction "K_2") (pintype "passive"))
      (node (ref "LED2") (pin "2") (pinfunction "K_2") (pintype "passive"))
      (node (ref "LED3") (pin "2") (pinfunction "K_2") (pintype "passive"))
      (node (ref "LED4") (pin "2") (pinfunction "K_2") (pintype "passive"))
      (node (ref "LED5") (pin "2") (pinfunction "K_2") (pintype "passive"))
      (node (ref "LED6") (pin "2") (pinfunction "K_2") (pintype "passive"))
      (node (ref "P2") (pin "1") (pinfunction "1_1") (pintype "passive"))
      (node (ref "R5") (pin "1") (pinfunction "1_1") (pintype "passive"))
      (node (ref "SW1") (pin "2") (pinfunction "2_2") (pintype "passive"))
      (node (ref "U1") (pin "15") (pinfunction "CLK_INH_15") (pintype "input"))
      (node (ref "U1") (pin "8") (pinfunction "GND_8") (pintype "passive"))
      (node (ref "U10") (pin "1") (pinfunction "GND_1") (pintype "power_in"))
      (node (ref "U11") (pin "15") (pinfunction "CLK_INH_15") (pintype "input"))
      (node (ref "U11") (pin "8") (pinfunction "GND_8") (pintype "passive"))
      (node (ref "U2") (pin "23") (pinfunction "VSS_1_23") (pintype "power_in"))
      (node (ref "U2") (pin "35") (pinfunction "VSS_2_35") (pintype "power_in"))
      (node (ref "U2") (pin "47") (pinfunction "VSS_3_47") (pintype "power_in"))
      (node (ref "U2") (pin "8") (pinfunction "VSSA_8") (pintype "power_in"))
      (node (ref "U3") (pin "8") (pinfunction "GND_8") (pintype "passive"))
      (node (ref "U4") (pin "8") (pinfunction "GND_8") (pintype "passive"))
      (node (ref "U5") (pin "8") (pinfunction "GND_8") (pintype "passive"))
      (node (ref "U6") (pin "15") (pinfunction "CLK_INH_15") (pintype "input"))
      (node (ref "U6") (pin "8") (pinfunction "GND_8") (pintype "passive"))
      (node (ref "U7") (pin "2") (pinfunction "GND_2") (pintype "passive"))
      (node (ref "U8") (pin "15") (pinfunction "CLK_INH_15") (pintype "input"))
      (node (ref "U8") (pin "8") (pinfunction "GND_8") (pintype "passive"))
      (node (ref "U9") (pin "1") (pinfunction "ADJ/GND_1") (pintype "power_in"))
    )
    (net (code "70") (name "Net-(D1-A)") (class "Default")
      (node (ref "D1") (pin "1") (pinfunction "A_1") (pintype "passive"))
      (node (ref "J1") (pin "1") (pinfunction "VBUS_1") (pintype "passive"))
    )
    (net (code "71") (name "Net-(D2-A)") (class "Default")
      (node (ref "D2") (pin "1") (pinfunction "A_1") (pintype "passive"))
      (node (ref "J2") (pin "1") (pinfunction "VBUS_1") (pintype "passive"))
    )
    (net (code "72") (name "Net-(LED1-A)") (class "Default")
      (node (ref "LED1") (pin "1") (pinfunction "A_1") (pintype "passive"))
      (node (ref "R1") (pin "2") (pinfunction "2_2") (pintype "passive"))
    )
    (net (code "73") (name "Net-(LED2-A)") (class "Default")
      (node (ref "LED2") (pin "1") (pinfunction "A_1") (pintype "passive"))
      (node (ref "R2") (pin "2") (pinfunction "2_2") (pintype "passive"))
    )
    (net (code "74") (name "Net-(LED3-A)") (class "Default")
      (node (ref "LED3") (pin "1") (pinfunction "A_1") (pintype "passive"))
      (node (ref "R3") (pin "1") (pinfunction "1_1") (pintype "passive"))
    )
    (net (code "75") (name "Net-(LED4-A)") (class "Default")
      (node (ref "LED4") (pin "1") (pinfunction "A_1") (pintype "passive"))
      (node (ref "R4") (pin "2") (pinfunction "2_2") (pintype "passive"))
    )
    (net (code "76") (name "Net-(LED5-A)") (class "Default")
      (node (ref "LED5") (pin "1") (pinfunction "A_1") (pintype "passive"))
      (node (ref "R7") (pin "1") (pinfunction "1_1") (pintype "passive"))
    )
    (net (code "77") (name "Net-(LED6-A)") (class "Default")
      (node (ref "LED6") (pin "1") (pinfunction "A_1") (pintype "passive"))
      (node (ref "R8") (pin "2") (pinfunction "2_2") (pintype "passive"))
    )
    (net (code "78") (name "Net-(LED7-A)") (class "Default")
      (node (ref "LED7") (pin "1") (pinfunction "A_1") (pintype "passive"))
      (node (ref "R9") (pin "1") (pinfunction "1_1") (pintype "passive"))
    )
    (net (code "79") (name "Net-(LED8-A)") (class "Default")
      (node (ref "LED8") (pin "1") (pinfunction "A_1") (pintype "passive"))
      (node (ref "R10") (pin "1") (pinfunction "1_1") (pintype "passive"))
    )
    (net (code "80") (name "Net-(U2A-BOOT0)") (class "Default")
      (node (ref "P1") (pin "1") (pinfunction "1_1") (pintype "passive"))
      (node (ref "R5") (pin "2") (pinfunction "2_2") (pintype "passive"))
      (node (ref "U2") (pin "44") (pinfunction "BOOT0_44") (pintype "input"))
    )
    (net (code "81") (name "Net-(U2A-PA0-WKUP)") (class "Default")
      (node (ref "R4") (pin "1") (pinfunction "1_1") (pintype "passive"))
      (node (ref "U2") (pin "10") (pinfunction "PA0-WKUP_10") (pintype "bidirectional"))
    )
    (net (code "82") (name "Net-(U2A-PA15)") (class "Default")
      (node (ref "R3") (pin "2") (pinfunction "2_2") (pintype "passive"))
      (node (ref "U2") (pin "38") (pinfunction "PA15_38") (pintype "bidirectional"))
    )
    (net (code "83") (name "Net-(U2A-PB0)") (class "Default")
      (node (ref "R1") (pin "1") (pinfunction "1_1") (pintype "passive"))
      (node (ref "U2") (pin "18") (pinfunction "PB0_18") (pintype "bidirectional"))
    )
    (net (code "84") (name "Net-(U2A-PB1)") (class "Default")
      (node (ref "R2") (pin "1") (pinfunction "1_1") (pintype "passive"))
      (node (ref "U2") (pin "19") (pinfunction "PB1_19") (pintype "bidirectional"))
    )
    (net (code "85") (name "Net-(U2A-PD0-OSC_IN)") (class "Default")
      (node (ref "C1") (pin "1") (pinfunction "1_1") (pintype "passive"))
      (node (ref "U2") (pin "5") (pinfunction "PD0-OSC_IN_5") (pintype "bidirectional"))
      (node (ref "Y1") (pin "2") (pinfunction "2_2") (pintype "passive"))
    )
    (net (code "86") (name "Net-(U2A-PD1-OSC_OUT)") (class "Default")
      (node (ref "C2") (pin "1") (pinfunction "1_1") (pintype "passive"))
      (node (ref "U2") (pin "6") (pinfunction "PD1-OSC_OUT_6") (pintype "bidirectional"))
      (node (ref "Y1") (pin "1") (pinfunction "1_1") (pintype "passive"))
    )
    (net (code "87") (name "Net-(U4-QH')") (class "Default")
      (node (ref "U4") (pin "9") (pinfunction "QH'_9") (pintype "input"))
      (node (ref "U5") (pin "14") (pinfunction "SER_14") (pintype "input"))
    )
    (net (code "88") (name "Net-(U8-SER)") (class "Default")
      (node (ref "U6") (pin "9") (pinfunction "Qh_9") (pintype "input"))
      (node (ref "U8") (pin "10") (pinfunction "SER_10") (pintype "input"))
    )
    (net (code "89") (name "Net-(U10-XI)") (class "Default")
      (node (ref "C12") (pin "1") (pinfunction "1_1") (pintype "passive"))
      (node (ref "U10") (pin "7") (pinfunction "XI_7") (pintype "input"))
      (node (ref "Y2") (pin "1") (pinfunction "1_1") (pintype "passive"))
    )
    (net (code "90") (name "Net-(U10-XO)") (class "Default")
      (node (ref "C13") (pin "1") (pinfunction "1_1") (pintype "passive"))
      (node (ref "U10") (pin "8") (pinfunction "XO_8") (pintype "output"))
      (node (ref "Y2") (pin "2") (pinfunction "2_2") (pintype "passive"))
    )
    (net (code "91") (name "unconnected-(EC1-+16V-Pad2)") (class "Default")
      (node (ref "EC1") (pin "2") (pinfunction "+16V_2") (pintype "input"))
    )
    (net (code "92") (name "unconnected-(EC1--16V-Pad52)") (class "Default")
      (node (ref "EC1") (pin "52") (pinfunction "-16V_52") (pintype "input"))
    )
    (net (code "93") (name "unconnected-(EC1-A16  -Pad16)") (class "Default")
      (node (ref "EC1") (pin "16") (pinfunction "A16  _16") (pintype "input"))
    )
    (net (code "94") (name "unconnected-(EC1-A17-Pad17)") (class "Default")
      (node (ref "EC1") (pin "17") (pinfunction "A17_17") (pintype "input"))
    )
    (net (code "95") (name "unconnected-(EC1-A18 -Pad15)") (class "Default")
      (node (ref "EC1") (pin "15") (pinfunction "A18 _15") (pintype "input"))
    )
    (net (code "96") (name "unconnected-(EC1-A19-Pad59)") (class "Default")
      (node (ref "EC1") (pin "59") (pinfunction "A19_59") (pintype "input"))
    )
    (net (code "97") (name "unconnected-(EC1-A20-Pad61)") (class "Default")
      (node (ref "EC1") (pin "61") (pinfunction "A20_61") (pintype "input"))
    )
    (net (code "98") (name "unconnected-(EC1-A21-Pad62)") (class "Default")
      (node (ref "EC1") (pin "62") (pinfunction "A21_62") (pintype "input"))
    )
    (net (code "99") (name "unconnected-(EC1-A22-Pad63)") (class "Default")
      (node (ref "EC1") (pin "63") (pinfunction "A22_63") (pintype "input"))
    )
    (net (code "100") (name "unconnected-(EC1-A23-Pad64)") (class "Default")
      (node (ref "EC1") (pin "64") (pinfunction "A23_64") (pintype "input"))
    )
    (net (code "101") (name "unconnected-(EC1-CLOCK -Pad49)") (class "Default")
      (node (ref "EC1") (pin "49") (pinfunction "CLOCK _49") (pintype "input"))
    )
    (net (code "102") (name "unconnected-(EC1-DMA_0*-Pad55)") (class "Default")
      (node (ref "EC1") (pin "55") (pinfunction "DMA_0*_55") (pintype "input"))
    )
    (net (code "103") (name "unconnected-(EC1-DMA_1*-Pad56)") (class "Default")
      (node (ref "EC1") (pin "56") (pinfunction "DMA_1*_56") (pintype "input"))
    )
    (net (code "104") (name "unconnected-(EC1-DMA_2*-Pad57)") (class "Default")
      (node (ref "EC1") (pin "57") (pinfunction "DMA_2*_57") (pintype "input"))
    )
    (net (code "105") (name "unconnected-(EC1-DMA_3*-Pad14)") (class "Default")
      (node (ref "EC1") (pin "14") (pinfunction "DMA_3*_14") (pintype "input"))
    )
    (net (code "106") (name "unconnected-(EC1-ERROR*-Pad98)") (class "Default")
      (node (ref "EC1") (pin "98") (pinfunction "ERROR*_98") (pintype "input"))
    )
    (net (code "107") (name "unconnected-(EC1-HOLD* -Pad74)") (class "Default")
      (node (ref "EC1") (pin "74") (pinfunction "HOLD* _74") (pintype "input"))
    )
    (net (code "108") (name "unconnected-(EC1-MWRT-Pad68)") (class "Default")
      (node (ref "EC1") (pin "68") (pinfunction "MWRT_68") (pintype "input"))
    )
    (net (code "109") (name "unconnected-(EC1-NDEF-Pad21)") (class "Default")
      (node (ref "EC1") (pin "21") (pinfunction "NDEF_21") (pintype "input"))
    )
    (net (code "110") (name "unconnected-(EC1-NDEF-Pad65)") (class "Default")
      (node (ref "EC1") (pin "65") (pinfunction "NDEF_65") (pintype "input"))
    )
    (net (code "111") (name "unconnected-(EC1-NDEF-Pad66)") (class "Default")
      (node (ref "EC1") (pin "66") (pinfunction "NDEF_66") (pintype "input"))
    )
    (net (code "112") (name "unconnected-(EC1-NMI*-Pad12)") (class "Default")
      (node (ref "EC1") (pin "12") (pinfunction "NMI*_12") (pintype "input"))
    )
    (net (code "113") (name "unconnected-(EC1-PHANTOM*-Pad67)") (class "Default")
      (node (ref "EC1") (pin "67") (pinfunction "PHANTOM*_67") (pintype "input"))
    )
    (net (code "114") (name "unconnected-(EC1-PHI-Pad24)") (class "Default")
      (node (ref "EC1") (pin "24") (pinfunction "PHI_24") (pintype "input"))
    )
    (net (code "115") (name "unconnected-(EC1-POC*-Pad99)") (class "Default")
      (node (ref "EC1") (pin "99") (pinfunction "POC*_99") (pintype "input"))
    )
    (net (code "116") (name "unconnected-(EC1-PWRFAIL*-Pad13)") (class "Default")
      (node (ref "EC1") (pin "13") (pinfunction "PWRFAIL*_13") (pintype "input"))
    )
    (net (code "117") (name "unconnected-(EC1-RDY-Pad72)") (class "Default")
      (node (ref "EC1") (pin "72") (pinfunction "RDY_72") (pintype "input"))
    )
    (net (code "118") (name "unconnected-(EC1-RESET*-Pad75)") (class "Default")
      (node (ref "EC1") (pin "75") (pinfunction "RESET*_75") (pintype "input"))
    )
    (net (code "119") (name "unconnected-(EC1-RFU-Pad27)") (class "Default")
      (node (ref "EC1") (pin "27") (pinfunction "RFU_27") (pintype "input"))
    )
    (net (code "120") (name "unconnected-(EC1-RFU-Pad28)") (class "Default")
      (node (ref "EC1") (pin "28") (pinfunction "RFU_28") (pintype "input"))
    )
    (net (code "121") (name "unconnected-(EC1-RFU-Pad69)") (class "Default")
      (node (ref "EC1") (pin "69") (pinfunction "RFU_69") (pintype "input"))
    )
    (net (code "122") (name "unconnected-(EC1-RFU-Pad71)") (class "Default")
      (node (ref "EC1") (pin "71") (pinfunction "RFU_71") (pintype "input"))
    )
    (net (code "123") (name "unconnected-(EC1-SIXTN*-Pad60)") (class "Default")
      (node (ref "EC1") (pin "60") (pinfunction "SIXTN*_60") (pintype "input"))
    )
    (net (code "124") (name "unconnected-(EC1-SLAVE_CLR*-Pad54)") (class "Default")
      (node (ref "EC1") (pin "54") (pinfunction "SLAVE_CLR*_54") (pintype "input"))
    )
    (net (code "125") (name "unconnected-(EC1-VI0-Pad4)") (class "Default")
      (node (ref "EC1") (pin "4") (pinfunction "VI0_4") (pintype "input"))
    )
    (net (code "126") (name "unconnected-(EC1-VI1-Pad5)") (class "Default")
      (node (ref "EC1") (pin "5") (pinfunction "VI1_5") (pintype "input"))
    )
    (net (code "127") (name "unconnected-(EC1-VI2-Pad6)") (class "Default")
      (node (ref "EC1") (pin "6") (pinfunction "VI2_6") (pintype "input"))
    )
    (net (code "128") (name "unconnected-(EC1-VI3-Pad7)") (class "Default")
      (node (ref "EC1") (pin "7") (pinfunction "VI3_7") (pintype "input"))
    )
    (net (code "129") (name "unconnected-(EC1-VI4-Pad8)") (class "Default")
      (node (ref "EC1") (pin "8") (pinfunction "VI4_8") (pintype "input"))
    )
    (net (code "130") (name "unconnected-(EC1-VI5-Pad9)") (class "Default")
      (node (ref "EC1") (pin "9") (pinfunction "VI5_9") (pintype "input"))
    )
    (net (code "131") (name "unconnected-(EC1-VI6-Pad10)") (class "Default")
      (node (ref "EC1") (pin "10") (pinfunction "VI6_10") (pintype "input"))
    )
    (net (code "132") (name "unconnected-(EC1-VI7-Pad11)") (class "Default")
      (node (ref "EC1") (pin "11") (pinfunction "VI7_11") (pintype "input"))
    )
    (net (code "133") (name "unconnected-(EC1-pDBIN  -Pad78)") (class "Default")
      (node (ref "EC1") (pin "78") (pinfunction "pDBIN  _78") (pintype "input"))
    )
    (net (code "134") (name "unconnected-(EC1-pHLDA-Pad26)") (class "Default")
      (node (ref "EC1") (pin "26") (pinfunction "pHLDA_26") (pintype "input"))
    )
    (net (code "135") (name "unconnected-(EC1-pSTVAL*-Pad25)") (class "Default")
      (node (ref "EC1") (pin "25") (pinfunction "pSTVAL*_25") (pintype "input"))
    )
    (net (code "136") (name "unconnected-(EC1-pSYNC-Pad76)") (class "Default")
      (node (ref "EC1") (pin "76") (pinfunction "pSYNC_76") (pintype "input"))
    )
    (net (code "137") (name "unconnected-(EC1-sHLTA-Pad48)") (class "Default")
      (node (ref "EC1") (pin "48") (pinfunction "sHLTA_48") (pintype "input"))
    )
    (net (code "138") (name "unconnected-(EC1-sINTA-Pad96)") (class "Default")
      (node (ref "EC1") (pin "96") (pinfunction "sINTA_96") (pintype "input"))
    )
    (net (code "139") (name "unconnected-(EC1-sWO*-Pad97)") (class "Default")
      (node (ref "EC1") (pin "97") (pinfunction "sWO*_97") (pintype "input"))
    )
    (net (code "140") (name "unconnected-(EC1-sXTRQ*-Pad58)") (class "Default")
      (node (ref "EC1") (pin "58") (pinfunction "sXTRQ*_58") (pintype "input"))
    )
    (net (code "141") (name "unconnected-(J1-SHELL-Pad5)") (class "Default")
      (node (ref "J1") (pin "5") (pinfunction "SHELL_5") (pintype "passive"))
    )
    (net (code "142") (name "unconnected-(J2-ID-Pad4)") (class "Default")
      (node (ref "J2") (pin "4") (pinfunction "ID_4") (pintype "passive"))
    )
    (net (code "143") (name "unconnected-(J2-SHIELD-Pad6)") (class "Default")
      (node (ref "J2") (pin "6") (pinfunction "SHIELD_6") (pintype "passive"))
    )
    (net (code "144") (name "unconnected-(U1-Qh-Pad7)") (class "Default")
      (node (ref "U1") (pin "7") (pinfunction "Qh_7") (pintype "input"))
    )
    (net (code "145") (name "unconnected-(U2A-PC13-TAMPER-RTC-Pad2)") (class "Default")
      (node (ref "U2") (pin "2") (pinfunction "PC13-TAMPER-RTC_2") (pintype "bidirectional"))
    )
    (net (code "146") (name "unconnected-(U2A-PC14-OSC32_IN-Pad3)") (class "Default")
      (node (ref "U2") (pin "3") (pinfunction "PC14-OSC32_IN_3") (pintype "bidirectional"))
    )
    (net (code "147") (name "unconnected-(U2A-PC15-OSC32_OUT-Pad4)") (class "Default")
      (node (ref "U2") (pin "4") (pinfunction "PC15-OSC32_OUT_4") (pintype "bidirectional"))
    )
    (net (code "148") (name "unconnected-(U2B-VBAT-Pad1)") (class "Default")
      (node (ref "U2") (pin "1") (pinfunction "VBAT_1") (pintype "power_in"))
    )
    (net (code "149") (name "unconnected-(U3-QH'-Pad9)") (class "Default")
      (node (ref "U3") (pin "9") (pinfunction "QH'_9") (pintype "input"))
    )
    (net (code "150") (name "unconnected-(U5-QH'-Pad9)") (class "Default")
      (node (ref "U5") (pin "9") (pinfunction "QH'_9") (pintype "input"))
    )
    (net (code "151") (name "unconnected-(U6-Qh-Pad7)") (class "Default")
      (node (ref "U6") (pin "7") (pinfunction "Qh_7") (pintype "input"))
    )
    (net (code "152") (name "unconnected-(U6-SER-Pad10)") (class "Default")
      (node (ref "U6") (pin "10") (pinfunction "SER_10") (pintype "input"))
    )
    (net (code "153") (name "unconnected-(U8-Qh-Pad7)") (class "Default")
      (node (ref "U8") (pin "7") (pinfunction "Qh_7") (pintype "input"))
    )
    (net (code "154") (name "unconnected-(U10-CTS-Pad9)") (class "Default")
      (node (ref "U10") (pin "9") (pinfunction "CTS_9") (pintype "input"))
    )
    (net (code "155") (name "unconnected-(U10-DCD-Pad12)") (class "Default")
      (node (ref "U10") (pin "12") (pinfunction "DCD_12") (pintype "input"))
    )
    (net (code "156") (name "unconnected-(U10-DSR-Pad10)") (class "Default")
      (node (ref "U10") (pin "10") (pinfunction "DSR_10") (pintype "input"))
    )
    (net (code "157") (name "unconnected-(U10-DTR-Pad13)") (class "Default")
      (node (ref "U10") (pin "13") (pinfunction "DTR_13") (pintype "output"))
    )
    (net (code "158") (name "unconnected-(U10-R232-Pad15)") (class "Default")
      (node (ref "U10") (pin "15") (pinfunction "R232_15") (pintype "input"))
    )
    (net (code "159") (name "unconnected-(U10-RI-Pad11)") (class "Default")
      (node (ref "U10") (pin "11") (pinfunction "RI_11") (pintype "input"))
    )
    (net (code "160") (name "unconnected-(U10-RTS-Pad14)") (class "Default")
      (node (ref "U10") (pin "14") (pinfunction "RTS_14") (pintype "output"))
    )
    (net (code "161") (name "unconnected-(U11-Qh-Pad7)") (class "Default")
      (node (ref "U11") (pin "7") (pinfunction "Qh_7") (pintype "input"))
    )
    (net (code "162") (name "unconnected-(U11-SER-Pad10)") (class "Default")
      (node (ref "U11") (pin "10") (pinfunction "SER_10") (pintype "input"))
    )
  )
)
